# esquematico.net
KiCad netlist of a schematic drawn in Altium Designer
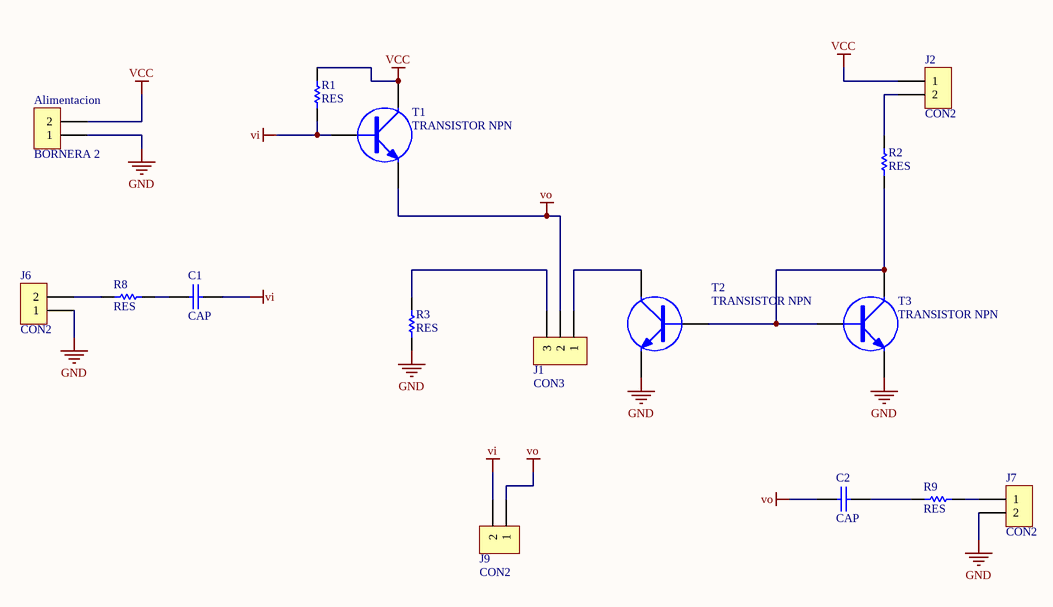
[diagram p0: esquematico.SchDoc]

(export (version "E")
  (design (tool "Eeschema 10.0.6"))
  (components
    (comp (ref "Alimentacion")
      (value "BORNERA 2")
      (footprint "BORNERA2")
      (libsource (lib "LIBEBAL") (part "BORNERA 2"))
    )
    (comp (ref "C1") (value "CAP") (footprint "CAP200") (libsource (lib "LIBEBAL") (part "CAP")))
    (comp (ref "C2") (value "CAP") (footprint "CAP200") (libsource (lib "LIBEBAL") (part "CAP")))
    (comp (ref "J1") (value "CON3") (footprint "SIP3") (libsource (lib "LIBEBAL") (part "CON3")))
    (comp (ref "J2") (value "CON2") (footprint "SIP2") (libsource (lib "LIBEBAL") (part "CON2")))
    (comp (ref "J6") (value "CON2") (footprint "SIP2") (libsource (lib "") (part "CON2_2")))
    (comp (ref "J7") (value "CON2") (footprint "SIP2") (libsource (lib "LIBEBAL") (part "CON2")))
    (comp (ref "J9") (value "CON2") (footprint "SIP2") (libsource (lib "") (part "CON2_1")))
    (comp (ref "R1") (value "RES") (footprint "RES400") (libsource (lib "LIBEBAL") (part "RES")))
    (comp (ref "R2") (value "RES") (footprint "RES400") (libsource (lib "LIBEBAL") (part "RES")))
    (comp (ref "R3") (value "RES") (footprint "RES400") (libsource (lib "LIBEBAL") (part "RES")))
    (comp (ref "R8") (value "RES") (footprint "RES400") (libsource (lib "LIBEBAL") (part "RES")))
    (comp (ref "R9") (value "RES") (footprint "RES400") (libsource (lib "LIBEBAL") (part "RES")))
    (comp (ref "T1")
      (value "TRANSISTOR NPN")
      (footprint "TO92")
      (libsource (lib "LIBEBAL") (part "TRANSISTOR NPN"))
    )
    (comp (ref "T2")
      (value "TRANSISTOR NPN")
      (footprint "TO92")
      (libsource (lib "LIBEBAL") (part "TRANSISTOR NPN"))
    )
    (comp (ref "T3")
      (value "TRANSISTOR NPN")
      (footprint "TO92")
      (libsource (lib "LIBEBAL") (part "TRANSISTOR NPN"))
    )
  )
  (nets
    (net (code "1") (name "GND") (class "Default")
      (node (ref "Alimentacion") (pin "1") (pinfunction "1_1") (pintype "passive"))
      (node (ref "J6") (pin "1") (pinfunction "1_1") (pintype "passive"))
      (node (ref "J7") (pin "2") (pinfunction "2_2") (pintype "passive"))
      (node (ref "R3") (pin "1") (pinfunction "1_1") (pintype "passive"))
      (node (ref "T2") (pin "3") (pinfunction "E_3") (pintype "passive"))
      (node (ref "T3") (pin "3") (pinfunction "E_3") (pintype "passive"))
    )
    (net (code "2") (name "Net-(C1-Pad1)") (class "Default")
      (node (ref "C1") (pin "1") (pinfunction "1_1") (pintype "passive"))
      (node (ref "R8") (pin "2") (pinfunction "2_2") (pintype "passive"))
    )
    (net (code "3") (name "Net-(C2-Pad2)") (class "Default")
      (node (ref "C2") (pin "2") (pinfunction "2_2") (pintype "passive"))
      (node (ref "R9") (pin "1") (pinfunction "1_1") (pintype "passive"))
    )
    (net (code "4") (name "Net-(J1-Pad3)") (class "Default")
      (node (ref "J1") (pin "3") (pinfunction "3_3") (pintype "passive"))
      (node (ref "R3") (pin "2") (pinfunction "2_2") (pintype "passive"))
    )
    (net (code "5") (name "Net-(J2-Pad2)") (class "Default")
      (node (ref "J2") (pin "2") (pinfunction "2_2") (pintype "passive"))
      (node (ref "R2") (pin "2") (pinfunction "2_2") (pintype "passive"))
    )
    (net (code "6") (name "Net-(J6-Pad2)") (class "Default")
      (node (ref "J6") (pin "2") (pinfunction "2_2") (pintype "passive"))
      (node (ref "R8") (pin "1") (pinfunction "1_1") (pintype "passive"))
    )
    (net (code "7") (name "Net-(J7-Pad1)") (class "Default")
      (node (ref "J7") (pin "1") (pinfunction "1_1") (pintype "passive"))
      (node (ref "R9") (pin "2") (pinfunction "2_2") (pintype "passive"))
    )
    (net (code "8") (name "Net-(T2-B)") (class "Default")
      (node (ref "R2") (pin "1") (pinfunction "1_1") (pintype "passive"))
      (node (ref "T2") (pin "1") (pinfunction "B_1") (pintype "passive"))
      (node (ref "T3") (pin "1") (pinfunction "B_1") (pintype "passive"))
      (node (ref "T3") (pin "2") (pinfunction "C_2") (pintype "passive"))
    )
    (net (code "9") (name "Net-(T2-C)") (class "Default")
      (node (ref "J1") (pin "1") (pinfunction "1_1") (pintype "passive"))
      (node (ref "T2") (pin "2") (pinfunction "C_2") (pintype "passive"))
    )
    (net (code "10") (name "VCC") (class "Default")
      (node (ref "Alimentacion") (pin "2") (pinfunction "2_2") (pintype "passive"))
      (node (ref "J2") (pin "1") (pinfunction "1_1") (pintype "passive"))
      (node (ref "R1") (pin "2") (pinfunction "2_2") (pintype "passive"))
      (node (ref "T1") (pin "2") (pinfunction "C_2") (pintype "passive"))
    )
    (net (code "11") (name "vi") (class "Default")
      (node (ref "C1") (pin "2") (pinfunction "2_2") (pintype "passive"))
      (node (ref "J9") (pin "2") (pinfunction "2_2") (pintype "passive"))
      (node (ref "R1") (pin "1") (pinfunction "1_1") (pintype "passive"))
      (node (ref "T1") (pin "1") (pinfunction "B_1") (pintype "passive"))
    )
    (net (code "12") (name "vo") (class "Default")
      (node (ref "C2") (pin "1") (pinfunction "1_1") (pintype "passive"))
      (node (ref "J1") (pin "2") (pinfunction "2_2") (pintype "passive"))
      (node (ref "J9") (pin "1") (pinfunction "1_1") (pintype "passive"))
      (node (ref "T1") (pin "3") (pinfunction "E_3") (pintype "passive"))
    )
  )
)
